# MagController.net
KiCad netlist of a schematic drawn in EAGLE
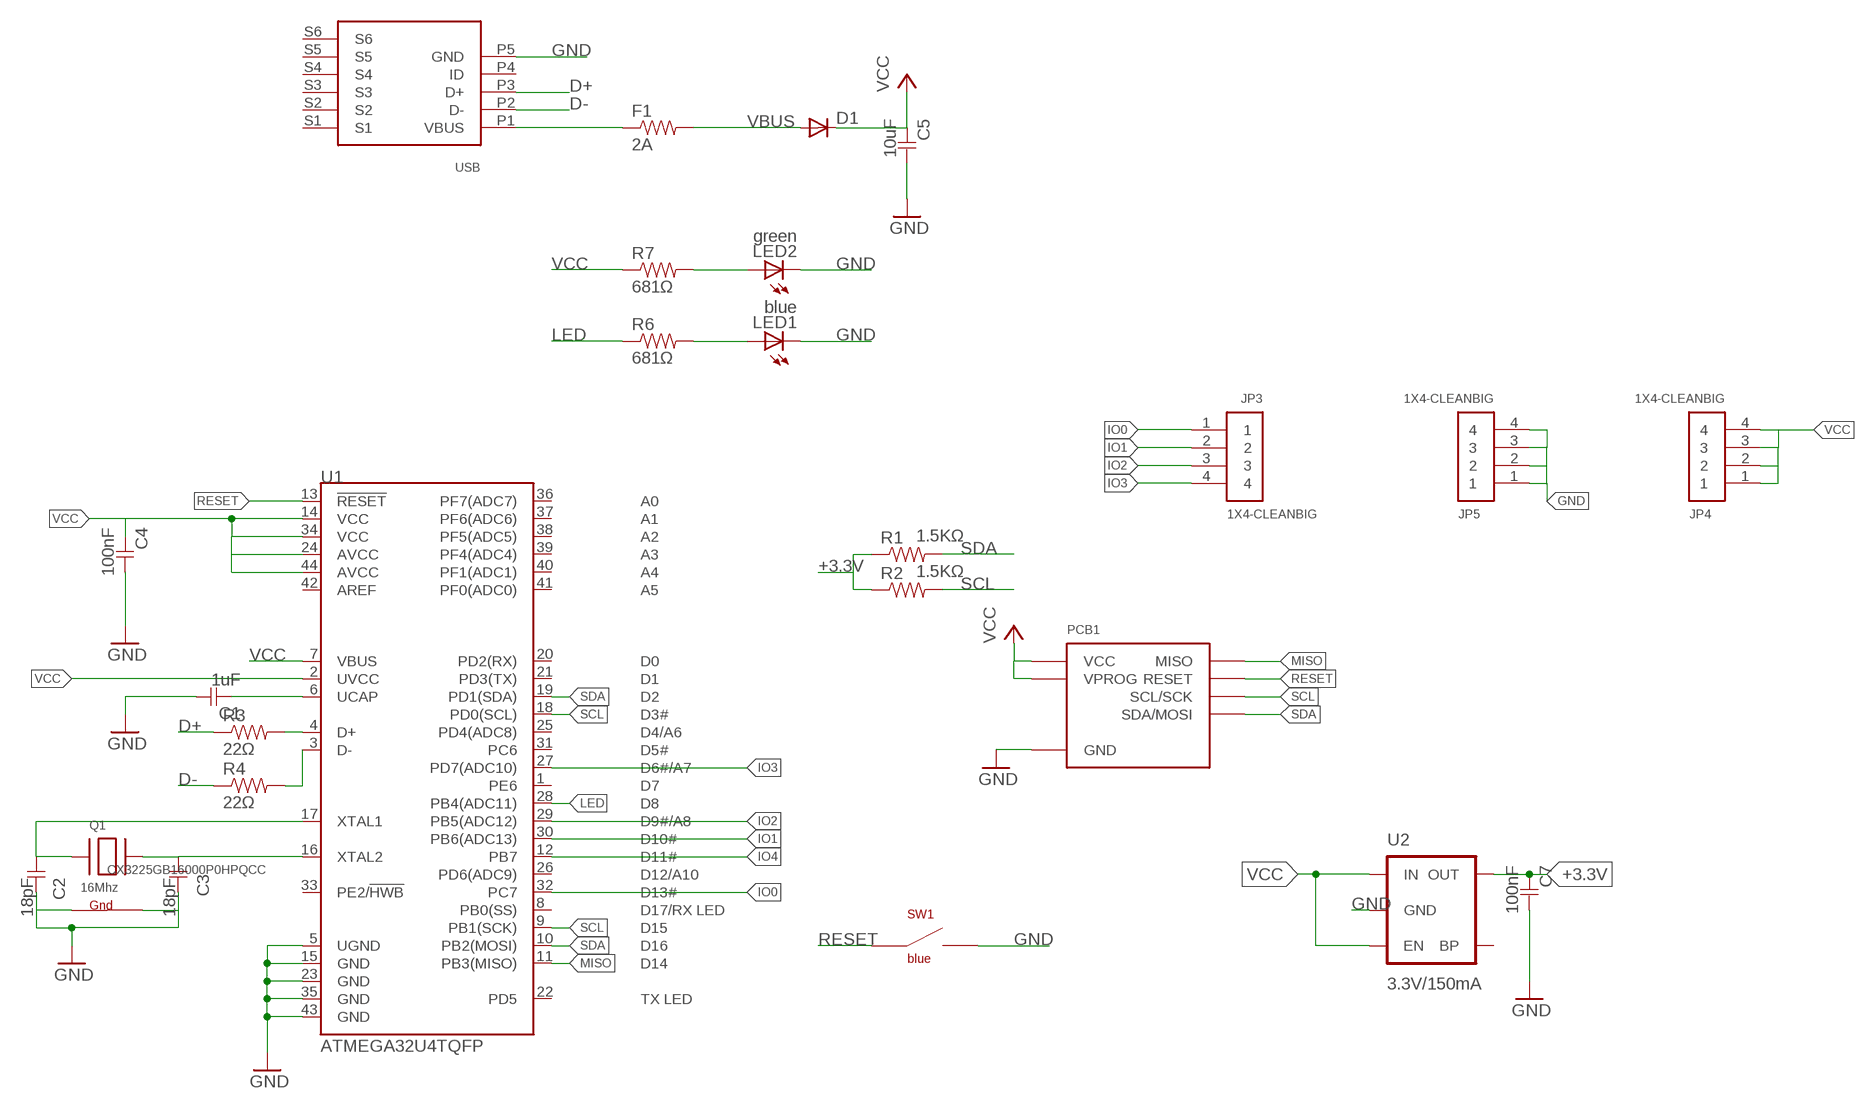
[diagram p0: schematic, sheet 1]

(export (version "E")
  (design (tool "Eeschema 10.0.6"))
  (components
    (comp (ref "C1")
      (value "1uF")
      (footprint "eagle-import:0603")
      (fields (field (name "PARTNUM") "C0603C105K4RACTU"))
      (libsource (lib "eagle-import") (part "CAPACITOR-1UF"))
    )
    (comp (ref "C2")
      (value "18pF")
      (footprint "eagle-import:0603")
      (fields (field (name "PARTNUM") "C0603C180J5GACTU"))
      (libsource (lib "eagle-import") (part "CAPACITOR-18PF"))
    )
    (comp (ref "C3")
      (value "18pF")
      (footprint "eagle-import:0603")
      (fields (field (name "PARTNUM") "C0603C180J5GACTU"))
      (libsource (lib "eagle-import") (part "CAPACITOR-18PF"))
    )
    (comp (ref "C4")
      (value "100nF")
      (footprint "eagle-import:0603")
      (fields (field (name "PARTNUM") "C0603C104K5RACTU"))
      (libsource (lib "eagle-import") (part "CAPACITOR-100NF"))
    )
    (comp (ref "C5")
      (value "10uF")
      (footprint "eagle-import:0603")
      (fields (field (name "PARTNUM") "GRM188R60J106ME47D"))
      (libsource (lib "eagle-import") (part "CAPACITOR-10UF"))
    )
    (comp (ref "C7")
      (value "100nF")
      (footprint "eagle-import:0603")
      (fields (field (name "PARTNUM") "C0603C104K5RACTU"))
      (libsource (lib "eagle-import") (part "CAPACITOR-100NF"))
    )
    (comp (ref "D1")
      (value "DIODESMA")
      (footprint "eagle-import:SMA-DIODE")
      (fields (field (name "PARTNUM") "SSA33L-E3/61TGICT-ND"))
      (libsource (lib "eagle-import") (part "DIODESMA"))
    )
    (comp (ref "F1")
      (value "2A")
      (footprint "eagle-import:0603")
      (fields (field (name "PARTNUM") "MF-PSMF110X-2"))
      (libsource (lib "eagle-import") (part "RESISTOR-0603"))
    )
    (comp (ref "JP3")
      (value "1X4-CLEANBIG")
      (footprint "eagle-import:1X04-CLEANBIG")
      (libsource (lib "eagle-import") (part "1X4-CLEANBIG"))
    )
    (comp (ref "JP4")
      (value "1X4-CLEANBIG")
      (footprint "eagle-import:1X04-CLEANBIG")
      (libsource (lib "eagle-import") (part "1X4-CLEANBIG"))
    )
    (comp (ref "JP5")
      (value "1X4-CLEANBIG")
      (footprint "eagle-import:1X04-CLEANBIG")
      (libsource (lib "eagle-import") (part "1X4-CLEANBIG"))
    )
    (comp (ref "LED1")
      (value "blue")
      (footprint "eagle-import:0805-LED")
      (fields (field (name "PARTNUM") "LTST-C171TBKT"))
      (libsource (lib "eagle-import") (part "LED-0805-BLUE"))
    )
    (comp (ref "LED2")
      (value "green")
      (footprint "eagle-import:0805-LED")
      (fields (field (name "PARTNUM") "LTST-C171GKT"))
      (libsource (lib "eagle-import") (part "LED-0805-GREEN"))
    )
    (comp (ref "PCB1")
      (value "MAGDEVICE-V2")
      (footprint "eagle-import:MAGDEVICE-V2")
      (libsource (lib "eagle-import") (part "MAGDEVICE-V2"))
    )
    (comp (ref "Q1")
      (value "16Mhz")
      (footprint "eagle-import:NX3225")
      (fields (field (name "PARTNUM") "CX3225GB16000P0HPQCC"))
      (libsource (lib "eagle-import") (part "CRYSTAL-NX3225"))
    )
    (comp (ref "R1")
      (value "1.5KΩ")
      (footprint "eagle-import:0603")
      (fields (field (name "PARTNUM") "ERJ-3EKF1501V"))
      (libsource (lib "eagle-import") (part "RESISTOR-1.5KΩ"))
    )
    (comp (ref "R2")
      (value "1.5KΩ")
      (footprint "eagle-import:0603")
      (fields (field (name "PARTNUM") "ERJ-3EKF1501V"))
      (libsource (lib "eagle-import") (part "RESISTOR-1.5KΩ"))
    )
    (comp (ref "R3")
      (value "22Ω")
      (footprint "eagle-import:0603")
      (fields (field (name "PARTNUM") "ERJ-3EKF22R0V"))
      (libsource (lib "eagle-import") (part "RESISTOR-22Ω"))
    )
    (comp (ref "R4")
      (value "22Ω")
      (footprint "eagle-import:0603")
      (fields (field (name "PARTNUM") "ERJ-3EKF22R0V"))
      (libsource (lib "eagle-import") (part "RESISTOR-22Ω"))
    )
    (comp (ref "R6")
      (value "681Ω")
      (footprint "eagle-import:0603")
      (fields (field (name "PARTNUM") "ERJ-3EKF6810V"))
      (libsource (lib "eagle-import") (part "RESISTOR-681Ω"))
    )
    (comp (ref "R7")
      (value "681Ω")
      (footprint "eagle-import:0603")
      (fields (field (name "PARTNUM") "ERJ-3EKF6810V"))
      (libsource (lib "eagle-import") (part "RESISTOR-681Ω"))
    )
    (comp (ref "SW1")
      (value "blue")
      (footprint "eagle-import:BOURNS-7914J")
      (fields (field (name "PARTNUM") "7914J-1-000E"))
      (libsource (lib "eagle-import") (part "SWITCHBOURNS-7914J"))
    )
    (comp (ref "U1")
      (value "ATMEGA32U4TQFP")
      (footprint "eagle-import:SPARKFUN-DIGITALIC_TQFP44")
      (fields (field (name "PARTNUM") "ATMEGA32U4-AU"))
      (libsource (lib "eagle-import") (part "ATMEGA32U4TQFP"))
    )
    (comp (ref "U2")
      (value "3.3V/150mA")
      (footprint "eagle-import:SOT23-5")
      (fields (field (name "PARTNUM") "MIC5205-3.3YM5 TR"))
      (libsource (lib "eagle-import") (part "V_REG_MIC52053.3V"))
    )
    (comp (ref "U3")
      (value "USBFCI-MICROB")
      (footprint "eagle-import:USB-MICROB-FCI")
      (fields (field (name "PARTNUM") "10118194-0001LF"))
      (libsource (lib "eagle-import") (part "USBFCI-MICROB"))
    )
  )
  (nets
    (net (code "1") (name "+3.3V") (class "Default")
      (node (ref "C7") (pin "1") (pinfunction "1_1") (pintype "passive"))
      (node (ref "R1") (pin "1") (pinfunction "1_1") (pintype "passive"))
      (node (ref "R2") (pin "1") (pinfunction "1_1") (pintype "passive"))
      (node (ref "U2") (pin "5") (pinfunction "OUT_5") (pintype "passive"))
    )
    (net (code "2") (name "/D+") (class "Default")
      (node (ref "R3") (pin "1") (pinfunction "1_1") (pintype "passive"))
      (node (ref "U3") (pin "P3") (pinfunction "D+_P3") (pintype "bidirectional"))
    )
    (net (code "3") (name "/D-") (class "Default")
      (node (ref "R4") (pin "1") (pinfunction "1_1") (pintype "passive"))
      (node (ref "U3") (pin "P2") (pinfunction "D-_P2") (pintype "bidirectional"))
    )
    (net (code "4") (name "/VBUS") (class "Default")
      (node (ref "D1") (pin "A") (pinfunction "A_A") (pintype "passive"))
      (node (ref "F1") (pin "2") (pinfunction "2_2") (pintype "passive"))
    )
    (net (code "5") (name "GND") (class "Default")
      (node (ref "C1") (pin "2") (pinfunction "2_2") (pintype "passive"))
      (node (ref "C2") (pin "2") (pinfunction "2_2") (pintype "passive"))
      (node (ref "C3") (pin "2") (pinfunction "2_2") (pintype "passive"))
      (node (ref "C4") (pin "2") (pinfunction "2_2") (pintype "passive"))
      (node (ref "C5") (pin "2") (pinfunction "2_2") (pintype "passive"))
      (node (ref "C7") (pin "2") (pinfunction "2_2") (pintype "passive"))
      (node (ref "JP5") (pin "1") (pinfunction "1_1") (pintype "bidirectional"))
      (node (ref "JP5") (pin "2") (pinfunction "2_2") (pintype "bidirectional"))
      (node (ref "JP5") (pin "3") (pinfunction "3_3") (pintype "bidirectional"))
      (node (ref "JP5") (pin "4") (pinfunction "4_4") (pintype "bidirectional"))
      (node (ref "LED1") (pin "C") (pinfunction "C_C") (pintype "passive"))
      (node (ref "LED2") (pin "C") (pinfunction "C_C") (pintype "passive"))
      (node (ref "PCB1") (pin "GND") (pinfunction "GND_GND") (pintype "bidirectional"))
      (node (ref "Q1") (pin "2") (pinfunction "G1_2") (pintype "power_in"))
      (node (ref "Q1") (pin "4") (pinfunction "G2_4") (pintype "power_in"))
      (node (ref "SW1") (pin "NEG$1") (pinfunction "NEG1_NEG$1") (pintype "bidirectional"))
      (node (ref "SW1") (pin "NEG$2") (pinfunction "NEG1_NEG$2") (pintype "bidirectional"))
      (node (ref "U1") (pin "15") (pinfunction "GND_15") (pintype "bidirectional"))
      (node (ref "U1") (pin "23") (pinfunction "GND_23") (pintype "bidirectional"))
      (node (ref "U1") (pin "35") (pinfunction "GND_35") (pintype "bidirectional"))
      (node (ref "U1") (pin "43") (pinfunction "GND_43") (pintype "bidirectional"))
      (node (ref "U1") (pin "5") (pinfunction "UGND_5") (pintype "bidirectional"))
      (node (ref "U2") (pin "2") (pinfunction "GND_2") (pintype "input"))
      (node (ref "U3") (pin "P5") (pinfunction "GND_P5") (pintype "bidirectional"))
    )
    (net (code "6") (name "IO0") (class "Default")
      (node (ref "JP3") (pin "1") (pinfunction "1_1") (pintype "bidirectional"))
      (node (ref "U1") (pin "32") (pinfunction "PC7_32") (pintype "bidirectional"))
    )
    (net (code "7") (name "IO1") (class "Default")
      (node (ref "JP3") (pin "2") (pinfunction "2_2") (pintype "bidirectional"))
      (node (ref "U1") (pin "30") (pinfunction "PB6(ADC13)_30") (pintype "bidirectional"))
    )
    (net (code "8") (name "IO2") (class "Default")
      (node (ref "JP3") (pin "3") (pinfunction "3_3") (pintype "bidirectional"))
      (node (ref "U1") (pin "29") (pinfunction "PB5(ADC12)_29") (pintype "bidirectional"))
    )
    (net (code "9") (name "IO3") (class "Default")
      (node (ref "JP3") (pin "4") (pinfunction "4_4") (pintype "bidirectional"))
      (node (ref "U1") (pin "27") (pinfunction "PD7(ADC10)_27") (pintype "bidirectional"))
    )
    (net (code "10") (name "IO4") (class "Default")
      (node (ref "U1") (pin "12") (pinfunction "PB7_12") (pintype "bidirectional"))
    )
    (net (code "11") (name "LED") (class "Default")
      (node (ref "R6") (pin "1") (pinfunction "1_1") (pintype "passive"))
      (node (ref "U1") (pin "28") (pinfunction "PB4(ADC11)_28") (pintype "bidirectional"))
    )
    (net (code "12") (name "MISO") (class "Default")
      (node (ref "PCB1") (pin "MISO") (pinfunction "MISO_MISO") (pintype "bidirectional"))
      (node (ref "U1") (pin "11") (pinfunction "PB3(MISO)_11") (pintype "bidirectional"))
    )
    (net (code "13") (name "Net-(LED1-PadA)") (class "Default")
      (node (ref "LED1") (pin "A") (pinfunction "A_A") (pintype "passive"))
      (node (ref "R6") (pin "2") (pinfunction "2_2") (pintype "passive"))
    )
    (net (code "14") (name "Net-(LED2-PadA)") (class "Default")
      (node (ref "LED2") (pin "A") (pinfunction "A_A") (pintype "passive"))
      (node (ref "R7") (pin "2") (pinfunction "2_2") (pintype "passive"))
    )
    (net (code "15") (name "Net-(Q1-X1)") (class "Default")
      (node (ref "C2") (pin "1") (pinfunction "1_1") (pintype "passive"))
      (node (ref "Q1") (pin "1") (pinfunction "X1_1") (pintype "bidirectional"))
      (node (ref "U1") (pin "17") (pinfunction "XTAL1_17") (pintype "bidirectional"))
    )
    (net (code "16") (name "Net-(Q1-X2)") (class "Default")
      (node (ref "C3") (pin "1") (pinfunction "1_1") (pintype "passive"))
      (node (ref "Q1") (pin "3") (pinfunction "X2_3") (pintype "bidirectional"))
      (node (ref "U1") (pin "16") (pinfunction "XTAL2_16") (pintype "bidirectional"))
    )
    (net (code "17") (name "Net-(U1-D+)") (class "Default")
      (node (ref "R3") (pin "2") (pinfunction "2_2") (pintype "passive"))
      (node (ref "U1") (pin "4") (pinfunction "D+_4") (pintype "bidirectional"))
    )
    (net (code "18") (name "Net-(U1-D-)") (class "Default")
      (node (ref "R4") (pin "2") (pinfunction "2_2") (pintype "passive"))
      (node (ref "U1") (pin "3") (pinfunction "D-_3") (pintype "bidirectional"))
    )
    (net (code "19") (name "Net-(U1-UCAP)") (class "Default")
      (node (ref "C1") (pin "1") (pinfunction "1_1") (pintype "passive"))
      (node (ref "U1") (pin "6") (pinfunction "UCAP_6") (pintype "bidirectional"))
    )
    (net (code "20") (name "Net-(U3-VBUS)") (class "Default")
      (node (ref "F1") (pin "1") (pinfunction "1_1") (pintype "passive"))
      (node (ref "U3") (pin "P1") (pinfunction "VBUS_P1") (pintype "bidirectional"))
    )
    (net (code "21") (name "RESET") (class "Default")
      (node (ref "PCB1") (pin "RESET") (pinfunction "RESET_RESET") (pintype "bidirectional"))
      (node (ref "SW1") (pin "POS$1") (pinfunction "POS1_POS$1") (pintype "bidirectional"))
      (node (ref "SW1") (pin "POS$2") (pinfunction "POS1_POS$2") (pintype "bidirectional"))
      (node (ref "U1") (pin "13") (pinfunction "~{RESET}_13") (pintype "bidirectional"))
    )
    (net (code "22") (name "SCL") (class "Default")
      (node (ref "PCB1") (pin "SCL") (pinfunction "SCL/SCK_SCL") (pintype "bidirectional"))
      (node (ref "R2") (pin "2") (pinfunction "2_2") (pintype "passive"))
      (node (ref "U1") (pin "18") (pinfunction "PD0(SCL)_18") (pintype "bidirectional"))
      (node (ref "U1") (pin "9") (pinfunction "PB1(SCK)_9") (pintype "bidirectional"))
    )
    (net (code "23") (name "SDA") (class "Default")
      (node (ref "PCB1") (pin "SDA") (pinfunction "SDA/MOSI_SDA") (pintype "bidirectional"))
      (node (ref "R1") (pin "2") (pinfunction "2_2") (pintype "passive"))
      (node (ref "U1") (pin "10") (pinfunction "PB2(MOSI)_10") (pintype "bidirectional"))
      (node (ref "U1") (pin "19") (pinfunction "PD1(SDA)_19") (pintype "bidirectional"))
    )
    (net (code "24") (name "VCC") (class "Default")
      (node (ref "C4") (pin "1") (pinfunction "1_1") (pintype "passive"))
      (node (ref "C5") (pin "1") (pinfunction "1_1") (pintype "passive"))
      (node (ref "D1") (pin "C") (pinfunction "C_C") (pintype "passive"))
      (node (ref "JP4") (pin "1") (pinfunction "1_1") (pintype "bidirectional"))
      (node (ref "JP4") (pin "2") (pinfunction "2_2") (pintype "bidirectional"))
      (node (ref "JP4") (pin "3") (pinfunction "3_3") (pintype "bidirectional"))
      (node (ref "JP4") (pin "4") (pinfunction "4_4") (pintype "bidirectional"))
      (node (ref "PCB1") (pin "VCC") (pinfunction "VCC_VCC") (pintype "bidirectional"))
      (node (ref "PCB1") (pin "VPROG") (pinfunction "VPROG_VPROG") (pintype "bidirectional"))
      (node (ref "R7") (pin "1") (pinfunction "1_1") (pintype "passive"))
      (node (ref "U1") (pin "14") (pinfunction "VCC_14") (pintype "bidirectional"))
      (node (ref "U1") (pin "2") (pinfunction "UVCC_2") (pintype "bidirectional"))
      (node (ref "U1") (pin "24") (pinfunction "AVCC_24") (pintype "bidirectional"))
      (node (ref "U1") (pin "34") (pinfunction "VCC_34") (pintype "bidirectional"))
      (node (ref "U1") (pin "44") (pinfunction "AVCC_44") (pintype "bidirectional"))
      (node (ref "U1") (pin "7") (pinfunction "VBUS_7") (pintype "bidirectional"))
      (node (ref "U2") (pin "1") (pinfunction "IN_1") (pintype "input"))
      (node (ref "U2") (pin "3") (pinfunction "EN_3") (pintype "input"))
    )
    (net (code "25") (name "unconnected-(U1-AREF-Pad42)") (class "Default")
      (node (ref "U1") (pin "42") (pinfunction "AREF_42") (pintype "bidirectional"))
    )
    (net (code "26") (name "unconnected-(U1-PB0(SS)-Pad8)") (class "Default")
      (node (ref "U1") (pin "8") (pinfunction "PB0(SS)_8") (pintype "bidirectional"))
    )
    (net (code "27") (name "unconnected-(U1-PC6-Pad31)") (class "Default")
      (node (ref "U1") (pin "31") (pinfunction "PC6_31") (pintype "bidirectional"))
    )
    (net (code "28") (name "unconnected-(U1-PD2(RX)-Pad20)") (class "Default")
      (node (ref "U1") (pin "20") (pinfunction "PD2(RX)_20") (pintype "bidirectional"))
    )
    (net (code "29") (name "unconnected-(U1-PD3(TX)-Pad21)") (class "Default")
      (node (ref "U1") (pin "21") (pinfunction "PD3(TX)_21") (pintype "bidirectional"))
    )
    (net (code "30") (name "unconnected-(U1-PD4(ADC8)-Pad25)") (class "Default")
      (node (ref "U1") (pin "25") (pinfunction "PD4(ADC8)_25") (pintype "bidirectional"))
    )
    (net (code "31") (name "unconnected-(U1-PD5-Pad22)") (class "Default")
      (node (ref "U1") (pin "22") (pinfunction "PD5_22") (pintype "bidirectional"))
    )
    (net (code "32") (name "unconnected-(U1-PD6(ADC9)-Pad26)") (class "Default")
      (node (ref "U1") (pin "26") (pinfunction "PD6(ADC9)_26") (pintype "bidirectional"))
    )
    (net (code "33") (name "unconnected-(U1-PE2{slash}~{HWB}-Pad33)") (class "Default")
      (node (ref "U1") (pin "33") (pinfunction "PE2/~{HWB}_33") (pintype "bidirectional"))
    )
    (net (code "34") (name "unconnected-(U1-PE6-Pad1)") (class "Default")
      (node (ref "U1") (pin "1") (pinfunction "PE6_1") (pintype "bidirectional"))
    )
    (net (code "35") (name "unconnected-(U1-PF0(ADC0)-Pad41)") (class "Default")
      (node (ref "U1") (pin "41") (pinfunction "PF0(ADC0)_41") (pintype "bidirectional"))
    )
    (net (code "36") (name "unconnected-(U1-PF1(ADC1)-Pad40)") (class "Default")
      (node (ref "U1") (pin "40") (pinfunction "PF1(ADC1)_40") (pintype "bidirectional"))
    )
    (net (code "37") (name "unconnected-(U1-PF4(ADC4)-Pad39)") (class "Default")
      (node (ref "U1") (pin "39") (pinfunction "PF4(ADC4)_39") (pintype "bidirectional"))
    )
    (net (code "38") (name "unconnected-(U1-PF5(ADC5)-Pad38)") (class "Default")
      (node (ref "U1") (pin "38") (pinfunction "PF5(ADC5)_38") (pintype "bidirectional"))
    )
    (net (code "39") (name "unconnected-(U1-PF6(ADC6)-Pad37)") (class "Default")
      (node (ref "U1") (pin "37") (pinfunction "PF6(ADC6)_37") (pintype "bidirectional"))
    )
    (net (code "40") (name "unconnected-(U1-PF7(ADC7)-Pad36)") (class "Default")
      (node (ref "U1") (pin "36") (pinfunction "PF7(ADC7)_36") (pintype "bidirectional"))
    )
    (net (code "41") (name "unconnected-(U2-BP-Pad4)") (class "Default")
      (node (ref "U2") (pin "4") (pinfunction "BP_4") (pintype "input"))
    )
    (net (code "42") (name "unconnected-(U3-ID-PadP4)") (class "Default")
      (node (ref "U3") (pin "P4") (pinfunction "ID_P4") (pintype "bidirectional"))
    )
    (net (code "43") (name "unconnected-(U3-PadS1)") (class "Default")
      (node (ref "U3") (pin "S1") (pinfunction "S1_S1") (pintype "bidirectional"))
    )
    (net (code "44") (name "unconnected-(U3-PadS2)") (class "Default")
      (node (ref "U3") (pin "S2") (pinfunction "S2_S2") (pintype "bidirectional"))
    )
    (net (code "45") (name "unconnected-(U3-PadS3)") (class "Default")
      (node (ref "U3") (pin "S3") (pinfunction "S3_S3") (pintype "bidirectional"))
    )
    (net (code "46") (name "unconnected-(U3-PadS4)") (class "Default")
      (node (ref "U3") (pin "S4") (pinfunction "S4_S4") (pintype "bidirectional"))
    )
    (net (code "47") (name "unconnected-(U3-PadS5)") (class "Default")
      (node (ref "U3") (pin "S5") (pinfunction "S5_S5") (pintype "bidirectional"))
    )
    (net (code "48") (name "unconnected-(U3-PadS6)") (class "Default")
      (node (ref "U3") (pin "S6") (pinfunction "S6_S6") (pintype "bidirectional"))
    )
  )
)
